# ut_mbed_programmer.net
KiCad netlist of a schematic drawn in Altium Designer
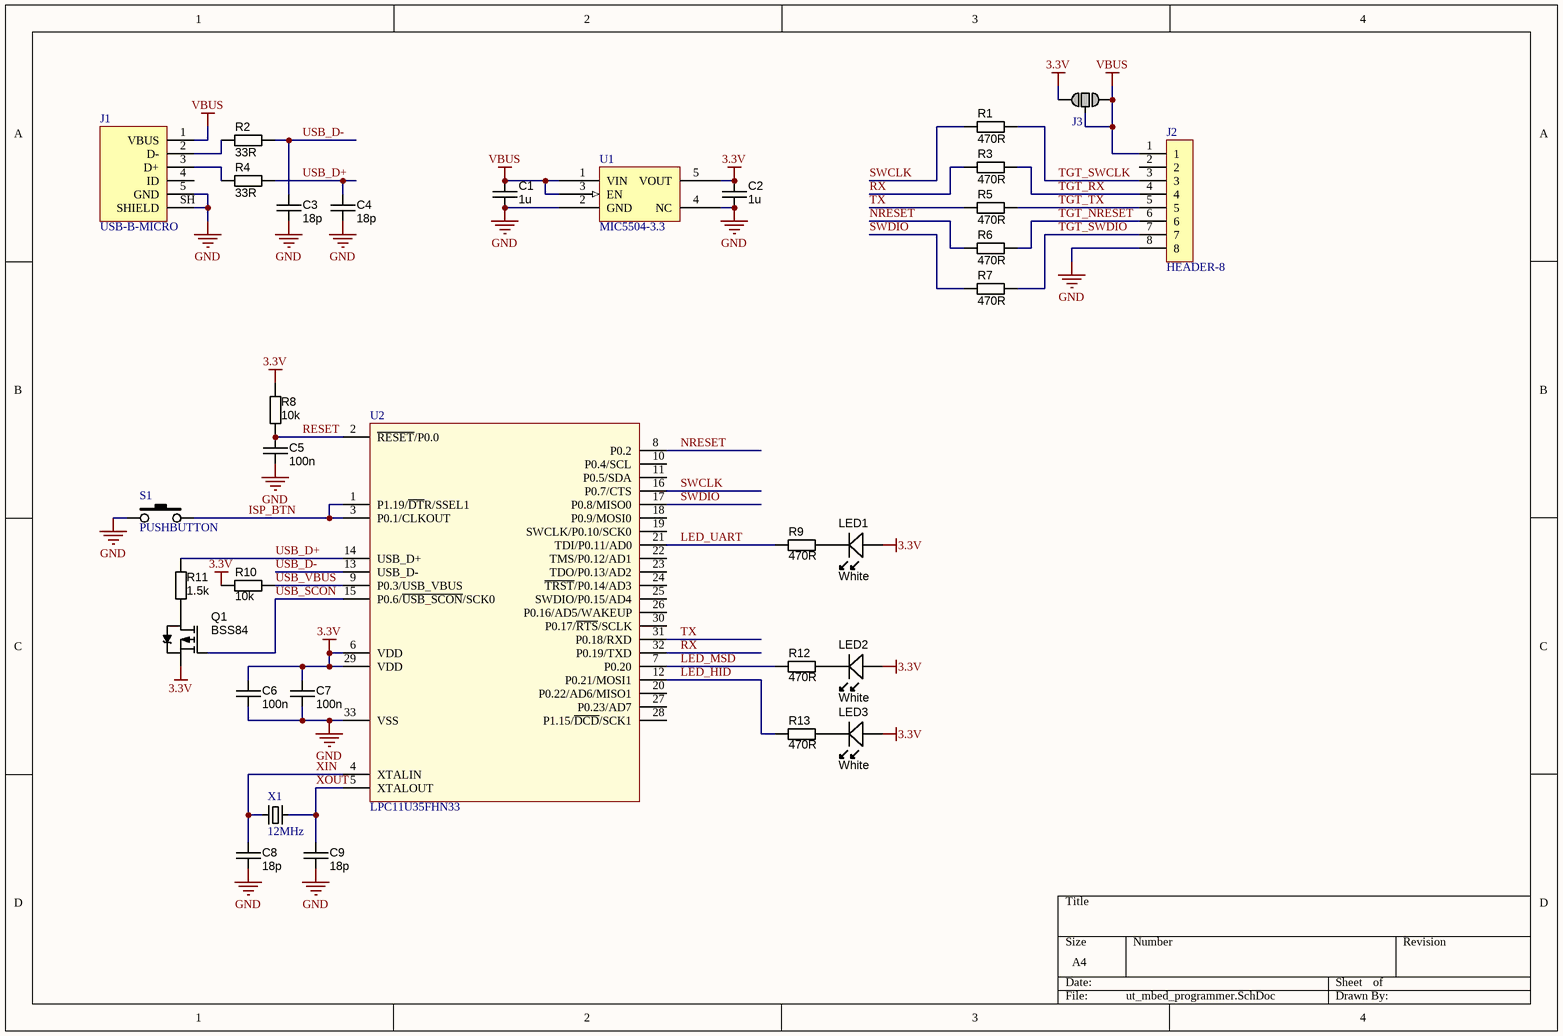
[diagram p0: ut_mbed_programmer.SchDoc]

(export (version "E")
  (design (tool "Eeschema 10.0.6"))
  (components
    (comp (ref "C1")
      (value "1u")
      (footprint "CAPC1608X90N")
      (description "Capacitor SMD Cer 1uF 10% 16V X7R 0603")
      (fields (field (name "TOLERANCE") "±10%"))
      (libsource (lib "PBL - Capacitors") (part "CAPC_1u_0603_X7R_16V_10%"))
    )
    (comp (ref "C2")
      (value "1u")
      (footprint "CAPC1608X90N")
      (description "Capacitor SMD Cer 1uF 10% 16V X7R 0603")
      (fields (field (name "TOLERANCE") "±10%"))
      (libsource (lib "PBL - Capacitors") (part "CAPC_1u_0603_X7R_16V_10%"))
    )
    (comp (ref "C3")
      (value "18p")
      (footprint "CAPC1608X90N")
      (description "Capacitor SMD Cer 8pF ±0.5pF 50V NP0 0603")
      (fields (field (name "TOLERANCE") "±0.5pF"))
      (libsource (lib "PBL - Capacitors") (part "CAPC_8p_0603_NP0_50V"))
    )
    (comp (ref "C4")
      (value "18p")
      (footprint "CAPC1608X90N")
      (description "Capacitor SMD Cer 8pF ±0.5pF 50V NP0 0603")
      (fields (field (name "TOLERANCE") "±0.5pF"))
      (libsource (lib "PBL - Capacitors") (part "CAPC_8p_0603_NP0_50V"))
    )
    (comp (ref "C5")
      (value "100n")
      (footprint "CAPC1608X90N")
      (description "Capacitor SMD Cer 8pF ±0.5pF 50V NP0 0603")
      (fields (field (name "TOLERANCE") "±0.5pF"))
      (libsource (lib "PBL - Capacitors") (part "CAPC_8p_0603_NP0_50V"))
    )
    (comp (ref "C6")
      (value "100n")
      (footprint "CAPC1608X90N")
      (description "Capacitor SMD Cer 8pF ±0.5pF 50V NP0 0603")
      (fields (field (name "TOLERANCE") "±0.5pF"))
      (libsource (lib "PBL - Capacitors") (part "CAPC_8p_0603_NP0_50V"))
    )
    (comp (ref "C7")
      (value "100n")
      (footprint "CAPC1608X90N")
      (description "Capacitor SMD Cer 8pF ±0.5pF 50V NP0 0603")
      (fields (field (name "TOLERANCE") "±0.5pF"))
      (libsource (lib "PBL - Capacitors") (part "CAPC_8p_0603_NP0_50V"))
    )
    (comp (ref "C8")
      (value "18p")
      (footprint "CAPC1608X90N")
      (description "Capacitor SMD Cer 8pF ±0.5pF 50V NP0 0603")
      (fields (field (name "TOLERANCE") "±0.5pF"))
      (libsource (lib "PBL - Capacitors") (part "CAPC_8p_0603_NP0_50V"))
    )
    (comp (ref "C9")
      (value "18p")
      (footprint "CAPC1608X90N")
      (description "Capacitor SMD Cer 8pF ±0.5pF 50V NP0 0603")
      (fields (field (name "TOLERANCE") "±0.5pF"))
      (libsource (lib "PBL - Capacitors") (part "CAPC_8p_0603_NP0_50V"))
    )
    (comp (ref "J1")
      (value "USB-B-MICRO")
      (footprint "USB-B-MICRO-FCI-10104110")
      (libsource (lib "connectors") (part "USB-B-MICRO"))
    )
    (comp (ref "J2")
      (value "HEADER-8")
      (footprint "MICRO-MATCH-FOB-08")
      (libsource (lib "connectors_micromatch") (part "HEADER-8"))
    )
    (comp (ref "J3")
      (value "JUMPER")
      (footprint "JUMPER-SMD-3WAY-1005")
      (libsource (lib "connectors") (part "JUMPER-SMD-3WAY"))
    )
    (comp (ref "LED1")
      (value "White")
      (footprint "LED-0603-WHITE")
      (description "LED 0603 SMD Bright White 8700K")
      (libsource (lib "PBL - Light Sources") (part "LED_SMD_White_0603_Bright"))
    )
    (comp (ref "LED2")
      (value "White")
      (footprint "LED-0603-WHITE")
      (description "LED 0603 SMD Bright White 8700K")
      (libsource (lib "PBL - Light Sources") (part "LED_SMD_White_0603_Bright"))
    )
    (comp (ref "LED3")
      (value "White")
      (footprint "LED-0603-WHITE")
      (description "LED 0603 SMD Bright White 8700K")
      (libsource (lib "PBL - Light Sources") (part "LED_SMD_White_0603_Bright"))
    )
    (comp (ref "Q1")
      (value "BSS84")
      (footprint "SOT23-3")
      (description "MOSFET SMD P-CH 50V 130mA SOT23-3")
      (libsource (lib "PBL - Transistors") (part "MOSFET_BSS84"))
    )
    (comp (ref "R1")
      (value "470R")
      (footprint "RESC1608X55N")
      (description "Resistor SMD chip 1k Ohm 0.1W 1% 0603")
      (fields (field (name "TOLERANCE") "±1%"))
      (libsource (lib "PBL - Resistors") (part "RES_1K_0603_1%"))
    )
    (comp (ref "R2")
      (value "33R")
      (footprint "RESC1608X55N")
      (description "Resistor SMD chip 1k Ohm 0.1W 1% 0603")
      (fields (field (name "TOLERANCE") "±1%"))
      (libsource (lib "PBL - Resistors") (part "RES_1K_0603_1%"))
    )
    (comp (ref "R3")
      (value "470R")
      (footprint "RESC1608X55N")
      (description "Resistor SMD chip 1k Ohm 0.1W 1% 0603")
      (fields (field (name "TOLERANCE") "±1%"))
      (libsource (lib "PBL - Resistors") (part "RES_1K_0603_1%"))
    )
    (comp (ref "R4")
      (value "33R")
      (footprint "RESC1608X55N")
      (description "Resistor SMD chip 1k Ohm 0.1W 1% 0603")
      (fields (field (name "TOLERANCE") "±1%"))
      (libsource (lib "PBL - Resistors") (part "RES_1K_0603_1%"))
    )
    (comp (ref "R5")
      (value "470R")
      (footprint "RESC1608X55N")
      (description "Resistor SMD chip 1k Ohm 0.1W 1% 0603")
      (fields (field (name "TOLERANCE") "±1%"))
      (libsource (lib "PBL - Resistors") (part "RES_1K_0603_1%"))
    )
    (comp (ref "R6")
      (value "470R")
      (footprint "RESC1608X55N")
      (description "Resistor SMD chip 1k Ohm 0.1W 1% 0603")
      (fields (field (name "TOLERANCE") "±1%"))
      (libsource (lib "PBL - Resistors") (part "RES_1K_0603_1%"))
    )
    (comp (ref "R7")
      (value "470R")
      (footprint "RESC1608X55N")
      (description "Resistor SMD chip 1k Ohm 0.1W 1% 0603")
      (fields (field (name "TOLERANCE") "±1%"))
      (libsource (lib "PBL - Resistors") (part "RES_1K_0603_1%"))
    )
    (comp (ref "R8")
      (value "10k")
      (footprint "RESC1608X55N")
      (description "Resistor SMD chip 1k Ohm 0.1W 1% 0603")
      (fields (field (name "TOLERANCE") "±1%"))
      (libsource (lib "") (part "RES_1K_0603_1%_2"))
    )
    (comp (ref "R9")
      (value "470R")
      (footprint "RESC1608X55N")
      (description "Resistor SMD chip 1k Ohm 0.1W 1% 0603")
      (fields (field (name "TOLERANCE") "±1%"))
      (libsource (lib "PBL - Resistors") (part "RES_1K_0603_1%"))
    )
    (comp (ref "R10")
      (value "10k")
      (footprint "RESC1608X55N")
      (description "Resistor SMD chip 1k Ohm 0.1W 1% 0603")
      (fields (field (name "TOLERANCE") "±1%"))
      (libsource (lib "") (part "RES_1K_0603_1%_1"))
    )
    (comp (ref "R11")
      (value "1.5k")
      (footprint "RESC1608X55N")
      (description "Resistor SMD chip 1k Ohm 0.1W 1% 0603")
      (fields (field (name "TOLERANCE") "±1%"))
      (libsource (lib "") (part "RES_1K_0603_1%_2"))
    )
    (comp (ref "R12")
      (value "470R")
      (footprint "RESC1608X55N")
      (description "Resistor SMD chip 1k Ohm 0.1W 1% 0603")
      (fields (field (name "TOLERANCE") "±1%"))
      (libsource (lib "PBL - Resistors") (part "RES_1K_0603_1%"))
    )
    (comp (ref "R13")
      (value "470R")
      (footprint "RESC1608X55N")
      (description "Resistor SMD chip 1k Ohm 0.1W 1% 0603")
      (fields (field (name "TOLERANCE") "±1%"))
      (libsource (lib "PBL - Resistors") (part "RES_1K_0603_1%"))
    )
    (comp (ref "S1")
      (value "PUSHBUTTON")
      (footprint "KMR421NGLFS")
      (libsource (lib "switches") (part "PUSHBUTTON"))
    )
    (comp (ref "U1")
      (value "MIC5504-3.3")
      (footprint "SOT23-5")
      (libsource (lib "power") (part "LDO-SOT23-5"))
    )
    (comp (ref "U2")
      (value "LPC11U35FHN33")
      (footprint "HVQFN33")
      (libsource (lib "nxp") (part "LPC11U35FHN33"))
    )
    (comp (ref "X1")
      (value "12MHz")
      (footprint "XTAL-3.2x2.5")
      (libsource (lib "misc") (part "XTAL-3.2X2.5"))
    )
  )
  (nets
    (net (code "1") (name "/ISP_BTN") (class "Default")
      (node (ref "S1") (pin "2") (pintype "passive"))
      (node (ref "U2") (pin "1") (pinfunction "P1.19/~{DT}R/SSEL1_1") (pintype "passive"))
      (node (ref "U2") (pin "3") (pinfunction "P0.1/CLKOUT_3") (pintype "passive"))
    )
    (net (code "2") (name "/LED_HID") (class "Default")
      (node (ref "R13") (pin "1") (pinfunction "1_1") (pintype "passive"))
      (node (ref "U2") (pin "12") (pinfunction "P0.21/MOSI1_12") (pintype "passive"))
    )
    (net (code "3") (name "/LED_MSD") (class "Default")
      (node (ref "R12") (pin "1") (pinfunction "1_1") (pintype "passive"))
      (node (ref "U2") (pin "7") (pinfunction "P0.20_7") (pintype "passive"))
    )
    (net (code "4") (name "/LED_UART") (class "Default")
      (node (ref "R9") (pin "1") (pinfunction "1_1") (pintype "passive"))
      (node (ref "U2") (pin "21") (pinfunction "TDI/P0.11/AD0_21") (pintype "passive"))
    )
    (net (code "5") (name "/NRESET") (class "Default")
      (node (ref "R6") (pin "1") (pinfunction "1_1") (pintype "passive"))
      (node (ref "U2") (pin "8") (pinfunction "P0.2_8") (pintype "passive"))
    )
    (net (code "6") (name "/RESET") (class "Default")
      (node (ref "C5") (pin "1") (pintype "passive"))
      (node (ref "R8") (pin "2") (pinfunction "2_2") (pintype "passive"))
      (node (ref "U2") (pin "2") (pinfunction "~{RESET}/P0.0_2") (pintype "passive"))
    )
    (net (code "7") (name "/RX") (class "Default")
      (node (ref "R3") (pin "1") (pinfunction "1_1") (pintype "passive"))
      (node (ref "U2") (pin "32") (pinfunction "P0.19/TXD_32") (pintype "passive"))
    )
    (net (code "8") (name "/SWCLK") (class "Default")
      (node (ref "R1") (pin "1") (pinfunction "1_1") (pintype "passive"))
      (node (ref "U2") (pin "16") (pinfunction "P0.7/CTS_16") (pintype "passive"))
    )
    (net (code "9") (name "/SWDIO") (class "Default")
      (node (ref "R7") (pin "1") (pinfunction "1_1") (pintype "passive"))
      (node (ref "U2") (pin "17") (pinfunction "P0.8/MISO0_17") (pintype "passive"))
    )
    (net (code "10") (name "/TGT_NRESET") (class "Default")
      (node (ref "J2") (pin "6") (pinfunction "6_6") (pintype "passive"))
      (node (ref "R6") (pin "2") (pinfunction "2_2") (pintype "passive"))
    )
    (net (code "11") (name "/TGT_RX") (class "Default")
      (node (ref "J2") (pin "4") (pinfunction "4_4") (pintype "passive"))
      (node (ref "R3") (pin "2") (pinfunction "2_2") (pintype "passive"))
    )
    (net (code "12") (name "/TGT_SWCLK") (class "Default")
      (node (ref "J2") (pin "3") (pinfunction "3_3") (pintype "passive"))
      (node (ref "R1") (pin "2") (pinfunction "2_2") (pintype "passive"))
    )
    (net (code "13") (name "/TGT_SWDIO") (class "Default")
      (node (ref "J2") (pin "7") (pinfunction "7_7") (pintype "passive"))
      (node (ref "R7") (pin "2") (pinfunction "2_2") (pintype "passive"))
    )
    (net (code "14") (name "/TGT_TX") (class "Default")
      (node (ref "J2") (pin "5") (pinfunction "5_5") (pintype "passive"))
      (node (ref "R5") (pin "2") (pinfunction "2_2") (pintype "passive"))
    )
    (net (code "15") (name "/TX") (class "Default")
      (node (ref "R5") (pin "1") (pinfunction "1_1") (pintype "passive"))
      (node (ref "U2") (pin "31") (pinfunction "P0.18/RXD_31") (pintype "passive"))
    )
    (net (code "16") (name "/USB_D+") (class "Default")
      (node (ref "C4") (pin "1") (pintype "passive"))
      (node (ref "R11") (pin "1") (pinfunction "1_1") (pintype "passive"))
      (node (ref "R4") (pin "2") (pinfunction "2_2") (pintype "passive"))
      (node (ref "U2") (pin "14") (pinfunction "USB_D+_14") (pintype "passive"))
    )
    (net (code "17") (name "/USB_D-") (class "Default")
      (node (ref "C3") (pin "1") (pintype "passive"))
      (node (ref "R2") (pin "2") (pinfunction "2_2") (pintype "passive"))
      (node (ref "U2") (pin "13") (pinfunction "USB_D-_13") (pintype "passive"))
    )
    (net (code "18") (name "/USB_SCON") (class "Default")
      (node (ref "Q1") (pin "1") (pinfunction "G_1") (pintype "passive"))
      (node (ref "U2") (pin "15") (pinfunction "P0.6/~{USB_SCON}/SCK0_15") (pintype "passive"))
    )
    (net (code "19") (name "/USB_VBUS") (class "Default")
      (node (ref "R10") (pin "1") (pinfunction "1_1") (pintype "passive"))
      (node (ref "U2") (pin "9") (pinfunction "P0.3/USB_VBUS_9") (pintype "passive"))
    )
    (net (code "20") (name "/XIN") (class "Default")
      (node (ref "C8") (pin "1") (pintype "passive"))
      (node (ref "U2") (pin "4") (pinfunction "XTALIN_4") (pintype "passive"))
      (node (ref "X1") (pin "1") (pinfunction "1_1") (pintype "passive"))
    )
    (net (code "21") (name "/XOUT") (class "Default")
      (node (ref "C9") (pin "1") (pintype "passive"))
      (node (ref "U2") (pin "5") (pinfunction "XTALOUT_5") (pintype "passive"))
      (node (ref "X1") (pin "3") (pinfunction "3_3") (pintype "passive"))
    )
    (net (code "22") (name "3.3V") (class "Default")
      (node (ref "C2") (pin "1") (pintype "passive"))
      (node (ref "C6") (pin "1") (pintype "passive"))
      (node (ref "C7") (pin "1") (pintype "passive"))
      (node (ref "J3") (pin "3") (pinfunction "3_3") (pintype "passive"))
      (node (ref "LED1") (pin "A") (pinfunction "A_A") (pintype "passive"))
      (node (ref "LED2") (pin "A") (pinfunction "A_A") (pintype "passive"))
      (node (ref "LED3") (pin "A") (pinfunction "A_A") (pintype "passive"))
      (node (ref "Q1") (pin "2") (pinfunction "S_2") (pintype "passive"))
      (node (ref "R10") (pin "2") (pinfunction "2_2") (pintype "passive"))
      (node (ref "R8") (pin "1") (pinfunction "1_1") (pintype "passive"))
      (node (ref "U1") (pin "5") (pinfunction "VOUT_5") (pintype "passive"))
      (node (ref "U2") (pin "29") (pinfunction "VDD_29") (pintype "passive"))
      (node (ref "U2") (pin "6") (pinfunction "VDD_6") (pintype "passive"))
    )
    (net (code "23") (name "GND") (class "Default")
      (node (ref "C1") (pin "2") (pintype "passive"))
      (node (ref "C2") (pin "2") (pintype "passive"))
      (node (ref "C3") (pin "2") (pintype "passive"))
      (node (ref "C4") (pin "2") (pintype "passive"))
      (node (ref "C5") (pin "2") (pintype "passive"))
      (node (ref "C6") (pin "2") (pintype "passive"))
      (node (ref "C7") (pin "2") (pintype "passive"))
      (node (ref "C8") (pin "2") (pintype "passive"))
      (node (ref "C9") (pin "2") (pintype "passive"))
      (node (ref "J1") (pin "5") (pinfunction "GND_5") (pintype "passive"))
      (node (ref "J1") (pin "SH") (pinfunction "SHIELD_SH") (pintype "passive"))
      (node (ref "J2") (pin "8") (pinfunction "8_8") (pintype "passive"))
      (node (ref "S1") (pin "1") (pintype "passive"))
      (node (ref "U1") (pin "2") (pinfunction "GND_2") (pintype "power_in"))
      (node (ref "U1") (pin "4") (pinfunction "NC_4") (pintype "power_in"))
      (node (ref "U2") (pin "33") (pinfunction "VSS_33") (pintype "passive"))
    )
    (net (code "24") (name "Net-(J1-D+)") (class "Default")
      (node (ref "J1") (pin "3") (pinfunction "D+_3") (pintype "passive"))
      (node (ref "R4") (pin "1") (pinfunction "1_1") (pintype "passive"))
    )
    (net (code "25") (name "Net-(J1-D-)") (class "Default")
      (node (ref "J1") (pin "2") (pinfunction "D-_2") (pintype "passive"))
      (node (ref "R2") (pin "1") (pinfunction "1_1") (pintype "passive"))
    )
    (net (code "26") (name "Net-(LED1-PadK)") (class "Default")
      (node (ref "LED1") (pin "K") (pinfunction "K_K") (pintype "passive"))
      (node (ref "R9") (pin "2") (pinfunction "2_2") (pintype "passive"))
    )
    (net (code "27") (name "Net-(LED2-PadK)") (class "Default")
      (node (ref "LED2") (pin "K") (pinfunction "K_K") (pintype "passive"))
      (node (ref "R12") (pin "2") (pinfunction "2_2") (pintype "passive"))
    )
    (net (code "28") (name "Net-(LED3-PadK)") (class "Default")
      (node (ref "LED3") (pin "K") (pinfunction "K_K") (pintype "passive"))
      (node (ref "R13") (pin "2") (pinfunction "2_2") (pintype "passive"))
    )
    (net (code "29") (name "Net-(Q1-D)") (class "Default")
      (node (ref "Q1") (pin "3") (pinfunction "D_3") (pintype "passive"))
      (node (ref "R11") (pin "2") (pinfunction "2_2") (pintype "passive"))
    )
    (net (code "30") (name "VBUS") (class "Default")
      (node (ref "C1") (pin "1") (pintype "passive"))
      (node (ref "J1") (pin "1") (pinfunction "VBUS_1") (pintype "passive"))
      (node (ref "J2") (pin "1") (pinfunction "1_1") (pintype "passive"))
      (node (ref "J3") (pin "1") (pinfunction "1_1") (pintype "passive"))
      (node (ref "J3") (pin "2") (pinfunction "2_2") (pintype "passive"))
      (node (ref "U1") (pin "1") (pinfunction "VIN_1") (pintype "power_in"))
      (node (ref "U1") (pin "3") (pinfunction "EN_3") (pintype "input"))
    )
    (net (code "31") (name "unconnected-(J1-ID-Pad4)") (class "Default")
      (node (ref "J1") (pin "4") (pinfunction "ID_4") (pintype "passive"))
    )
    (net (code "32") (name "unconnected-(J2-Pad2)") (class "Default")
      (node (ref "J2") (pin "2") (pinfunction "2_2") (pintype "passive"))
    )
    (net (code "33") (name "unconnected-(U2-P0.4{slash}SCL-Pad10)") (class "Default")
      (node (ref "U2") (pin "10") (pinfunction "P0.4/SCL_10") (pintype "passive"))
    )
    (net (code "34") (name "unconnected-(U2-P0.5{slash}SDA-Pad11)") (class "Default")
      (node (ref "U2") (pin "11") (pinfunction "P0.5/SDA_11") (pintype "passive"))
    )
    (net (code "35") (name "unconnected-(U2-P0.9{slash}MOSI0-Pad18)") (class "Default")
      (node (ref "U2") (pin "18") (pinfunction "P0.9/MOSI0_18") (pintype "passive"))
    )
    (net (code "36") (name "unconnected-(U2-P0.16{slash}AD5{slash}WAKEUP-Pad26)") (class "Default")
      (node (ref "U2") (pin "26") (pinfunction "P0.16/AD5/WAKEUP_26") (pintype "passive"))
    )
    (net (code "37") (name "unconnected-(U2-P0.17{slash}~{RTS}{slash}SCLK-Pad30)") (class "Default")
      (node (ref "U2") (pin "30") (pinfunction "P0.17/~{RTS}/SCLK_30") (pintype "passive"))
    )
    (net (code "38") (name "unconnected-(U2-P0.22{slash}AD6{slash}MISO1-Pad20)") (class "Default")
      (node (ref "U2") (pin "20") (pinfunction "P0.22/AD6/MISO1_20") (pintype "passive"))
    )
    (net (code "39") (name "unconnected-(U2-P0.23{slash}AD7-Pad27)") (class "Default")
      (node (ref "U2") (pin "27") (pinfunction "P0.23/AD7_27") (pintype "passive"))
    )
    (net (code "40") (name "unconnected-(U2-P1.15{slash}~{DCD}{slash}SCK1-Pad28)") (class "Default")
      (node (ref "U2") (pin "28") (pinfunction "P1.15/~{DCD}/SCK1_28") (pintype "passive"))
    )
    (net (code "41") (name "unconnected-(U2-SWCLK{slash}P0.10{slash}SCK0-Pad19)") (class "Default")
      (node (ref "U2") (pin "19") (pinfunction "SWCLK/P0.10/SCK0_19") (pintype "passive"))
    )
    (net (code "42") (name "unconnected-(U2-SWDIO{slash}P0.15{slash}AD4-Pad25)") (class "Default")
      (node (ref "U2") (pin "25") (pinfunction "SWDIO/P0.15/AD4_25") (pintype "passive"))
    )
    (net (code "43") (name "unconnected-(U2-TDO{slash}P0.13{slash}AD2-Pad23)") (class "Default")
      (node (ref "U2") (pin "23") (pinfunction "TDO/P0.13/AD2_23") (pintype "passive"))
    )
    (net (code "44") (name "unconnected-(U2-TMS{slash}P0.12{slash}AD1-Pad22)") (class "Default")
      (node (ref "U2") (pin "22") (pinfunction "TMS/P0.12/AD1_22") (pintype "passive"))
    )
    (net (code "45") (name "unconnected-(U2-~{TRST}{slash}P0.14{slash}AD3-Pad24)") (class "Default")
      (node (ref "U2") (pin "24") (pinfunction "~{TRST}/P0.14/AD3_24") (pintype "passive"))
    )
  )
)
